# wifi.net
KiCad netlist of a schematic drawn in Altium Designer
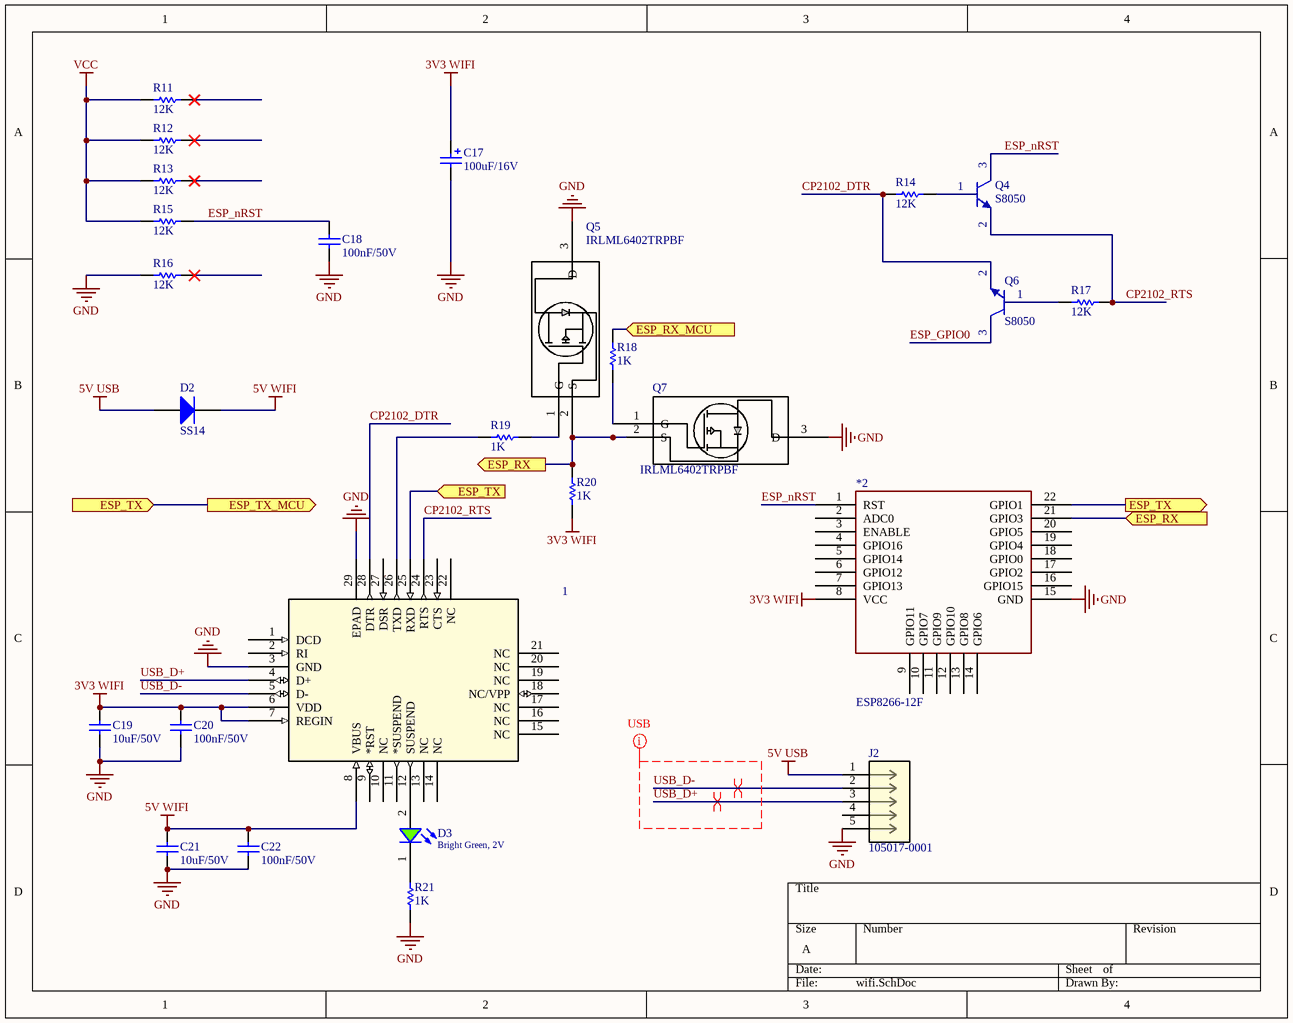
[diagram p0: wifi.SchDoc]

(export (version "E")
  (design (tool "Eeschema 10.0.6"))
  (components
    (comp (ref "*2")
      (value "ESP8266-12F")
      (footprint "ESP8266-12F")
      (fields (field (name "LOCAL SUPPLIER PART NUMBER") "HS000912"))
      (libsource (lib "PIF_robot") (part "ESP8266-12F"))
    )
    (comp (ref "1")
      (value "~")
      (footprint "QFN28_5X5_SIL")
      (description "No Description Available")
      (fields
        (field (name "MANUFACTURER_PART_NUMBER") "CP2102-GM")
        (field (name "COPYRIGHT") "Copyright (C) 2018 Accelerated Designs. All rights reserved")
      )
      (libsource (lib "2020-06-18_11-57-54") (part "CP2102-GM"))
    )
    (comp (ref "C17")
      (value "100uF/16V")
      (footprint "CAP_SM_TAN")
      (fields
        (field (name "MANUFACTURER") "Nichicon")
        (field (name "MANUFACTURER PART NUMBER") "UWX1C101MCL1GB")
        (field (name "Comment") "TAJB107M006RNJ")
      )
      (libsource (lib "Capacitor") (part "Cap-Tan-100uF-16V"))
    )
    (comp (ref "C18")
      (value "100nF/50V")
      (footprint "CAP-SM-0805")
      (description "CAP CER 0.1UF 50V Y5V 0805")
      (fields
        (field (name "MANUFACTURER") "Samsung Electro-Mechanics")
        (field (name "MANUFACTURER PART NUMBER") "CL21F104ZBCNNNC")
      )
      (libsource (lib "Capacitor") (part "Cap-100nF-50V-0805"))
    )
    (comp (ref "C19")
      (value "10uF/50V")
      (footprint "CAP-SM-0805")
      (description "CAP CER 10UF 50V X5R 0805")
      (fields
        (field (name "MANUFACTURER") "Yageo")
        (field (name "MANUFACTURER PART NUMBER") "CC0805KKX5R9BB106")
      )
      (libsource (lib "Capacitor") (part "Cap-10uF-50V-0805"))
    )
    (comp (ref "C20")
      (value "100nF/50V")
      (footprint "CAP-SM-0805")
      (description "CAP CER 0.1UF 50V Y5V 0805")
      (fields
        (field (name "MANUFACTURER") "Samsung Electro-Mechanics")
        (field (name "MANUFACTURER PART NUMBER") "CL21F104ZBCNNNC")
      )
      (libsource (lib "Capacitor") (part "Cap-100nF-50V-0805"))
    )
    (comp (ref "C21")
      (value "10uF/50V")
      (footprint "CAP-SM-0805")
      (description "CAP CER 10UF 50V X5R 0805")
      (fields
        (field (name "MANUFACTURER") "Yageo")
        (field (name "MANUFACTURER PART NUMBER") "CC0805KKX5R9BB106")
      )
      (libsource (lib "Capacitor") (part "Cap-10uF-50V-0805"))
    )
    (comp (ref "C22")
      (value "100nF/50V")
      (footprint "CAP-SM-0805")
      (description "CAP CER 0.1UF 50V Y5V 0805")
      (fields
        (field (name "MANUFACTURER") "Samsung Electro-Mechanics")
        (field (name "MANUFACTURER PART NUMBER") "CL21F104ZBCNNNC")
      )
      (libsource (lib "Capacitor") (part "Cap-100nF-50V-0805"))
    )
    (comp (ref "D2")
      (value "SS14")
      (footprint "SS14")
      (description "DIODE SCHOTTKY 40V 1A SMA")
      (fields (field (name "MANUFACTURER") "ON Semiconductor"))
      (libsource (lib "integrated_lib") (part "Diode-SS14"))
    )
    (comp (ref "D3")
      (value "Bright Green, 2V")
      (footprint "WL-SMCW_0805")
      (description "WL-SMCW SMT Mono-color Chip LED Waterclear, size 0805, Bright Green, 2V, 140deg")
      (fields (field (name "PART NUMBER") "150080VS75000") (field (name "PUBLISHER") "Wurth Elektronik"))
      (libsource (lib "150060BS75000_Altium_WL-SMCW_rev20a") (part "150080VS75000"))
    )
    (comp (ref "J2")
      (value "105017-0001")
      (footprint "CONN_105017-0001")
      (description "No Description Available")
      (fields (field (name "COPYRIGHT") "Copyright (C) 2018 Accelerated Designs. All rights reserved"))
      (libsource (lib "2020-06-20_08-55-21") (part "105017-0001"))
    )
    (comp (ref "Q4") (value "S8050") (footprint "SOT23_NEX") (libsource (lib "BJT") (part "S8050")))
    (comp (ref "Q5")
      (value "IRLML6402TRPBF")
      (footprint "SOT23_INF")
      (description "No Description Available")
      (fields (field (name "COPYRIGHT") "Copyright (C) 2018 Accelerated Designs. All rights reserved"))
      (libsource (lib "2020-06-20_07-22-20") (part "IRLML6402TRPBF"))
    )
    (comp (ref "Q6") (value "S8050") (footprint "SOT23_NEX") (libsource (lib "BJT") (part "S8050")))
    (comp (ref "Q7")
      (value "IRLML6402TRPBF")
      (footprint "SOT23_INF")
      (description "No Description Available")
      (fields (field (name "COPYRIGHT") "Copyright (C) 2018 Accelerated Designs. All rights reserved"))
      (libsource (lib "2020-06-20_07-22-20") (part "IRLML6402TRPBF"))
    )
    (comp (ref "R11")
      (value "12K")
      (footprint "Resistor:RES-SM-0805")
      (description "RES 12 KOHM JUMPER 0805")
      (fields
        (field (name "MANUFACTURER") "Vishay Thin Film")
        (field (name "MANUFACTURER PART NUMBER") "PAT0805E3121BST1")
      )
      (libsource (lib "Resistor") (part "Res-12K-0805"))
    )
    (comp (ref "R12")
      (value "12K")
      (footprint "Resistor:RES-SM-0805")
      (description "RES 12 KOHM JUMPER 0805")
      (fields
        (field (name "MANUFACTURER") "Vishay Thin Film")
        (field (name "MANUFACTURER PART NUMBER") "PAT0805E3121BST1")
      )
      (libsource (lib "Resistor") (part "Res-12K-0805"))
    )
    (comp (ref "R13")
      (value "12K")
      (footprint "Resistor:RES-SM-0805")
      (description "RES 12 KOHM JUMPER 0805")
      (fields
        (field (name "MANUFACTURER") "Vishay Thin Film")
        (field (name "MANUFACTURER PART NUMBER") "PAT0805E3121BST1")
      )
      (libsource (lib "Resistor") (part "Res-12K-0805"))
    )
    (comp (ref "R14")
      (value "12K")
      (footprint "Resistor:RES-SM-0805")
      (description "RES 12 KOHM JUMPER 0805")
      (fields
        (field (name "MANUFACTURER") "Vishay Thin Film")
        (field (name "MANUFACTURER PART NUMBER") "PAT0805E3121BST1")
      )
      (libsource (lib "Resistor") (part "Res-12K-0805"))
    )
    (comp (ref "R15")
      (value "12K")
      (footprint "Resistor:RES-SM-0805")
      (description "RES 12 KOHM JUMPER 0805")
      (fields
        (field (name "MANUFACTURER") "Vishay Thin Film")
        (field (name "MANUFACTURER PART NUMBER") "PAT0805E3121BST1")
      )
      (libsource (lib "Resistor") (part "Res-12K-0805"))
    )
    (comp (ref "R16")
      (value "12K")
      (footprint "Resistor:RES-SM-0805")
      (description "RES 12 KOHM JUMPER 0805")
      (fields
        (field (name "MANUFACTURER") "Vishay Thin Film")
        (field (name "MANUFACTURER PART NUMBER") "PAT0805E3121BST1")
      )
      (libsource (lib "Resistor") (part "Res-12K-0805"))
    )
    (comp (ref "R17")
      (value "12K")
      (footprint "Resistor:RES-SM-0805")
      (description "RES 12 KOHM JUMPER 0805")
      (fields
        (field (name "MANUFACTURER") "Vishay Thin Film")
        (field (name "MANUFACTURER PART NUMBER") "PAT0805E3121BST1")
      )
      (libsource (lib "Resistor") (part "Res-12K-0805"))
    )
    (comp (ref "R18")
      (value "1K")
      (footprint "Resistor:RES-SM-0805")
      (description "RES 1K OHM 1% 1/4W 0805")
      (fields
        (field (name "MANUFACTURER") "Stackpole Electronics Inc")
        (field (name "MANUFACTURER PART NUMBER") "RNCP0805FTD1K00")
      )
      (libsource (lib "Resistor") (part "Res-1K-0805"))
    )
    (comp (ref "R19")
      (value "1K")
      (footprint "Resistor:RES-SM-0805")
      (description "RES 1K OHM 1% 1/4W 0805")
      (fields
        (field (name "MANUFACTURER") "Stackpole Electronics Inc")
        (field (name "MANUFACTURER PART NUMBER") "RNCP0805FTD1K00")
      )
      (libsource (lib "Resistor") (part "Res-1K-0805"))
    )
    (comp (ref "R20")
      (value "1K")
      (footprint "Resistor:RES-SM-0805")
      (description "RES 1K OHM 1% 1/4W 0805")
      (fields
        (field (name "MANUFACTURER") "Stackpole Electronics Inc")
        (field (name "MANUFACTURER PART NUMBER") "RNCP0805FTD1K00")
      )
      (libsource (lib "Resistor") (part "Res-1K-0805"))
    )
    (comp (ref "R21")
      (value "1K")
      (footprint "Resistor:RES-SM-0805")
      (description "RES 1K OHM 1% 1/4W 0805")
      (fields
        (field (name "MANUFACTURER") "Stackpole Electronics Inc")
        (field (name "MANUFACTURER PART NUMBER") "RNCP0805FTD1K00")
      )
      (libsource (lib "Resistor") (part "Res-1K-0805"))
    )
  )
  (nets
    (net (code "1") (name "/CP2102_DTR") (class "Default")
      (node (ref "1") (pin "28") (pinfunction "DTR_28") (pintype "output"))
      (node (ref "Q6") (pin "2") (pinfunction "E_2") (pintype "passive"))
      (node (ref "R14") (pin "1") (pinfunction "1_1") (pintype "passive"))
    )
    (net (code "2") (name "/CP2102_RTS") (class "Default")
      (node (ref "1") (pin "24") (pinfunction "RTS_24") (pintype "output"))
      (node (ref "Q4") (pin "2") (pinfunction "E_2") (pintype "passive"))
      (node (ref "R17") (pin "2") (pinfunction "2_2") (pintype "passive"))
    )
    (net (code "3") (name "/ESP_GPIO0") (class "Default")
      (node (ref "Q6") (pin "3") (pinfunction "C_3") (pintype "passive"))
    )
    (net (code "4") (name "/ESP_RX") (class "Default")
      (node (ref "*2") (pin "21") (pinfunction "GPIO3_21") (pintype "passive"))
      (node (ref "Q5") (pin "2") (pinfunction "S_2") (pintype "passive"))
      (node (ref "Q7") (pin "2") (pinfunction "S_2") (pintype "passive"))
      (node (ref "R20") (pin "2") (pinfunction "2_2") (pintype "passive"))
    )
    (net (code "5") (name "/ESP_RX_MCU") (class "Default")
      (node (ref "R18") (pin "1") (pinfunction "1_1") (pintype "passive"))
    )
    (net (code "6") (name "/ESP_TX") (class "Default")
      (node (ref "*2") (pin "22") (pinfunction "GPIO1_22") (pintype "passive"))
      (node (ref "1") (pin "25") (pinfunction "RXD_25") (pintype "input"))
    )
    (net (code "7") (name "/ESP_nRST") (class "Default")
      (node (ref "*2") (pin "1") (pinfunction "RST_1") (pintype "passive"))
      (node (ref "C18") (pin "2") (pinfunction "2_2") (pintype "passive"))
      (node (ref "Q4") (pin "3") (pinfunction "C_3") (pintype "passive"))
      (node (ref "R15") (pin "2") (pinfunction "2_2") (pintype "passive"))
    )
    (net (code "8") (name "/USB_D+") (class "Default")
      (node (ref "1") (pin "4") (pinfunction "D+_4") (pintype "bidirectional"))
      (node (ref "J2") (pin "3") (pinfunction "3_3") (pintype "passive"))
    )
    (net (code "9") (name "/USB_D-") (class "Default")
      (node (ref "1") (pin "5") (pinfunction "D-_5") (pintype "bidirectional"))
      (node (ref "J2") (pin "2") (pinfunction "2_2") (pintype "passive"))
    )
    (net (code "10") (name "3V3 WIFI") (class "Default")
      (node (ref "*2") (pin "8") (pinfunction "VCC_8") (pintype "passive"))
      (node (ref "1") (pin "6") (pinfunction "VDD_6") (pintype "power_in"))
      (node (ref "1") (pin "7") (pinfunction "REGIN_7") (pintype "input"))
      (node (ref "C17") (pin "1") (pinfunction "1_1") (pintype "passive"))
      (node (ref "C19") (pin "2") (pinfunction "2_2") (pintype "passive"))
      (node (ref "C20") (pin "2") (pinfunction "2_2") (pintype "passive"))
      (node (ref "R20") (pin "1") (pinfunction "1_1") (pintype "passive"))
    )
    (net (code "11") (name "5V USB") (class "Default")
      (node (ref "D2") (pin "2") (pinfunction "A_2") (pintype "passive"))
      (node (ref "J2") (pin "1") (pinfunction "1_1") (pintype "passive"))
    )
    (net (code "12") (name "5V WIFI") (class "Default")
      (node (ref "1") (pin "8") (pinfunction "VBUS_8") (pintype "input"))
      (node (ref "C21") (pin "2") (pinfunction "2_2") (pintype "passive"))
      (node (ref "C22") (pin "2") (pinfunction "2_2") (pintype "passive"))
      (node (ref "D2") (pin "1") (pinfunction "K_1") (pintype "passive"))
    )
    (net (code "13") (name "GND") (class "Default")
      (node (ref "*2") (pin "15") (pinfunction "GND_15") (pintype "passive"))
      (node (ref "1") (pin "29") (pinfunction "EPAD_29") (pintype "passive"))
      (node (ref "1") (pin "3") (pinfunction "GND_3") (pintype "power_in"))
      (node (ref "C17") (pin "2") (pinfunction "2_2") (pintype "passive"))
      (node (ref "C18") (pin "1") (pinfunction "1_1") (pintype "passive"))
      (node (ref "C19") (pin "1") (pinfunction "1_1") (pintype "passive"))
      (node (ref "C20") (pin "1") (pinfunction "1_1") (pintype "passive"))
      (node (ref "C21") (pin "1") (pinfunction "1_1") (pintype "passive"))
      (node (ref "C22") (pin "1") (pinfunction "1_1") (pintype "passive"))
      (node (ref "J2") (pin "5") (pinfunction "5_5") (pintype "passive"))
      (node (ref "Q5") (pin "3") (pinfunction "D_3") (pintype "passive"))
      (node (ref "Q7") (pin "3") (pinfunction "D_3") (pintype "passive"))
      (node (ref "R16") (pin "1") (pinfunction "1_1") (pintype "passive"))
      (node (ref "R21") (pin "1") (pinfunction "1_1") (pintype "passive"))
    )
    (net (code "14") (name "Net-(1-SUSPEND)") (class "Default")
      (node (ref "1") (pin "12") (pinfunction "SUSPEND_12") (pintype "output"))
      (node (ref "D3") (pin "2") (pinfunction "A_2") (pintype "passive"))
    )
    (net (code "15") (name "Net-(1-TXD)") (class "Default")
      (node (ref "1") (pin "26") (pinfunction "TXD_26") (pintype "output"))
      (node (ref "R19") (pin "1") (pinfunction "1_1") (pintype "passive"))
    )
    (net (code "16") (name "Net-(D3-K)") (class "Default")
      (node (ref "D3") (pin "1") (pinfunction "K_1") (pintype "passive"))
      (node (ref "R21") (pin "2") (pinfunction "2_2") (pintype "passive"))
    )
    (net (code "17") (name "Net-(Q4-B)") (class "Default")
      (node (ref "Q4") (pin "1") (pinfunction "B_1") (pintype "passive"))
      (node (ref "R14") (pin "2") (pinfunction "2_2") (pintype "passive"))
    )
    (net (code "18") (name "Net-(Q5-G)") (class "Default")
      (node (ref "Q5") (pin "1") (pinfunction "G_1") (pintype "passive"))
      (node (ref "R19") (pin "2") (pinfunction "2_2") (pintype "passive"))
    )
    (net (code "19") (name "Net-(Q6-B)") (class "Default")
      (node (ref "Q6") (pin "1") (pinfunction "B_1") (pintype "passive"))
      (node (ref "R17") (pin "1") (pinfunction "1_1") (pintype "passive"))
    )
    (net (code "20") (name "Net-(Q7-G)") (class "Default")
      (node (ref "Q7") (pin "1") (pinfunction "G_1") (pintype "passive"))
      (node (ref "R18") (pin "2") (pinfunction "2_2") (pintype "passive"))
    )
    (net (code "21") (name "VCC") (class "Default")
      (node (ref "R11") (pin "1") (pinfunction "1_1") (pintype "passive"))
      (node (ref "R12") (pin "1") (pinfunction "1_1") (pintype "passive"))
      (node (ref "R13") (pin "1") (pinfunction "1_1") (pintype "passive"))
      (node (ref "R15") (pin "1") (pinfunction "1_1") (pintype "passive"))
    )
    (net (code "22") (name "unconnected-(*2-ADC0-Pad2)") (class "Default")
      (node (ref "*2") (pin "2") (pinfunction "ADC0_2") (pintype "passive"))
    )
    (net (code "23") (name "unconnected-(*2-ENABLE-Pad3)") (class "Default")
      (node (ref "*2") (pin "3") (pinfunction "ENABLE_3") (pintype "passive"))
    )
    (net (code "24") (name "unconnected-(*2-GPIO0-Pad18)") (class "Default")
      (node (ref "*2") (pin "18") (pinfunction "GPIO0_18") (pintype "passive"))
    )
    (net (code "25") (name "unconnected-(*2-GPIO2-Pad17)") (class "Default")
      (node (ref "*2") (pin "17") (pinfunction "GPIO2_17") (pintype "passive"))
    )
    (net (code "26") (name "unconnected-(*2-GPIO4-Pad19)") (class "Default")
      (node (ref "*2") (pin "19") (pinfunction "GPIO4_19") (pintype "passive"))
    )
    (net (code "27") (name "unconnected-(*2-GPIO5-Pad20)") (class "Default")
      (node (ref "*2") (pin "20") (pinfunction "GPIO5_20") (pintype "passive"))
    )
    (net (code "28") (name "unconnected-(*2-GPIO6-Pad14)") (class "Default")
      (node (ref "*2") (pin "14") (pinfunction "GPIO6_14") (pintype "passive"))
    )
    (net (code "29") (name "unconnected-(*2-GPIO7-Pad10)") (class "Default")
      (node (ref "*2") (pin "10") (pinfunction "GPIO7_10") (pintype "passive"))
    )
    (net (code "30") (name "unconnected-(*2-GPIO8-Pad13)") (class "Default")
      (node (ref "*2") (pin "13") (pinfunction "GPIO8_13") (pintype "passive"))
    )
    (net (code "31") (name "unconnected-(*2-GPIO9-Pad11)") (class "Default")
      (node (ref "*2") (pin "11") (pinfunction "GPIO9_11") (pintype "passive"))
    )
    (net (code "32") (name "unconnected-(*2-GPIO10-Pad12)") (class "Default")
      (node (ref "*2") (pin "12") (pinfunction "GPIO10_12") (pintype "passive"))
    )
    (net (code "33") (name "unconnected-(*2-GPIO11-Pad9)") (class "Default")
      (node (ref "*2") (pin "9") (pinfunction "GPIO11_9") (pintype "passive"))
    )
    (net (code "34") (name "unconnected-(*2-GPIO12-Pad6)") (class "Default")
      (node (ref "*2") (pin "6") (pinfunction "GPIO12_6") (pintype "passive"))
    )
    (net (code "35") (name "unconnected-(*2-GPIO13-Pad7)") (class "Default")
      (node (ref "*2") (pin "7") (pinfunction "GPIO13_7") (pintype "passive"))
    )
    (net (code "36") (name "unconnected-(*2-GPIO14-Pad5)") (class "Default")
      (node (ref "*2") (pin "5") (pinfunction "GPIO14_5") (pintype "passive"))
    )
    (net (code "37") (name "unconnected-(*2-GPIO15-Pad16)") (class "Default")
      (node (ref "*2") (pin "16") (pinfunction "GPIO15_16") (pintype "passive"))
    )
    (net (code "38") (name "unconnected-(*2-GPIO16-Pad4)") (class "Default")
      (node (ref "*2") (pin "4") (pinfunction "GPIO16_4") (pintype "passive"))
    )
    (net (code "39") (name "unconnected-(1-*RST-Pad9)") (class "Default")
      (node (ref "1") (pin "9") (pinfunction "*RST_9") (pintype "bidirectional"))
    )
    (net (code "40") (name "unconnected-(1-*SUSPEND-Pad11)") (class "Default")
      (node (ref "1") (pin "11") (pinfunction "*SUSPEND_11") (pintype "output"))
    )
    (net (code "41") (name "unconnected-(1-CTS-Pad23)") (class "Default")
      (node (ref "1") (pin "23") (pinfunction "CTS_23") (pintype "input"))
    )
    (net (code "42") (name "unconnected-(1-DCD-Pad1)") (class "Default")
      (node (ref "1") (pin "1") (pinfunction "DCD_1") (pintype "input"))
    )
    (net (code "43") (name "unconnected-(1-DSR-Pad27)") (class "Default")
      (node (ref "1") (pin "27") (pinfunction "DSR_27") (pintype "input"))
    )
    (net (code "44") (name "unconnected-(1-NC-Pad10)") (class "Default")
      (node (ref "1") (pin "10") (pinfunction "NC_10") (pintype "passive"))
    )
    (net (code "45") (name "unconnected-(1-NC-Pad13)") (class "Default")
      (node (ref "1") (pin "13") (pinfunction "NC_13") (pintype "passive"))
    )
    (net (code "46") (name "unconnected-(1-NC-Pad14)") (class "Default")
      (node (ref "1") (pin "14") (pinfunction "NC_14") (pintype "passive"))
    )
    (net (code "47") (name "unconnected-(1-NC-Pad15)") (class "Default")
      (node (ref "1") (pin "15") (pinfunction "NC_15") (pintype "passive"))
    )
    (net (code "48") (name "unconnected-(1-NC-Pad16)") (class "Default")
      (node (ref "1") (pin "16") (pinfunction "NC_16") (pintype "passive"))
    )
    (net (code "49") (name "unconnected-(1-NC-Pad17)") (class "Default")
      (node (ref "1") (pin "17") (pinfunction "NC_17") (pintype "passive"))
    )
    (net (code "50") (name "unconnected-(1-NC-Pad19)") (class "Default")
      (node (ref "1") (pin "19") (pinfunction "NC_19") (pintype "passive"))
    )
    (net (code "51") (name "unconnected-(1-NC-Pad20)") (class "Default")
      (node (ref "1") (pin "20") (pinfunction "NC_20") (pintype "passive"))
    )
    (net (code "52") (name "unconnected-(1-NC-Pad21)") (class "Default")
      (node (ref "1") (pin "21") (pinfunction "NC_21") (pintype "passive"))
    )
    (net (code "53") (name "unconnected-(1-NC-Pad22)") (class "Default")
      (node (ref "1") (pin "22") (pinfunction "NC_22") (pintype "passive"))
    )
    (net (code "54") (name "unconnected-(1-NC{slash}VPP-Pad18)") (class "Default")
      (node (ref "1") (pin "18") (pinfunction "NC/VPP_18") (pintype "bidirectional"))
    )
    (net (code "55") (name "unconnected-(1-RI-Pad2)") (class "Default")
      (node (ref "1") (pin "2") (pinfunction "RI_2") (pintype "input"))
    )
    (net (code "56") (name "unconnected-(J2-Pad4)") (class "Default")
      (node (ref "J2") (pin "4") (pinfunction "4_4") (pintype "passive"))
    )
    (net (code "57") (name "unconnected-(R11-Pad2)") (class "Default")
      (node (ref "R11") (pin "2") (pinfunction "2_2") (pintype "passive+no_connect"))
    )
    (net (code "58") (name "unconnected-(R12-Pad2)") (class "Default")
      (node (ref "R12") (pin "2") (pinfunction "2_2") (pintype "passive+no_connect"))
    )
    (net (code "59") (name "unconnected-(R13-Pad2)") (class "Default")
      (node (ref "R13") (pin "2") (pinfunction "2_2") (pintype "passive+no_connect"))
    )
    (net (code "60") (name "unconnected-(R16-Pad2)") (class "Default")
      (node (ref "R16") (pin "2") (pinfunction "2_2") (pintype "passive+no_connect"))
    )
  )
)
